# 2502_IDS_TransMax_PWM_Digital.net
KiCad netlist of a schematic drawn in Altium Designer
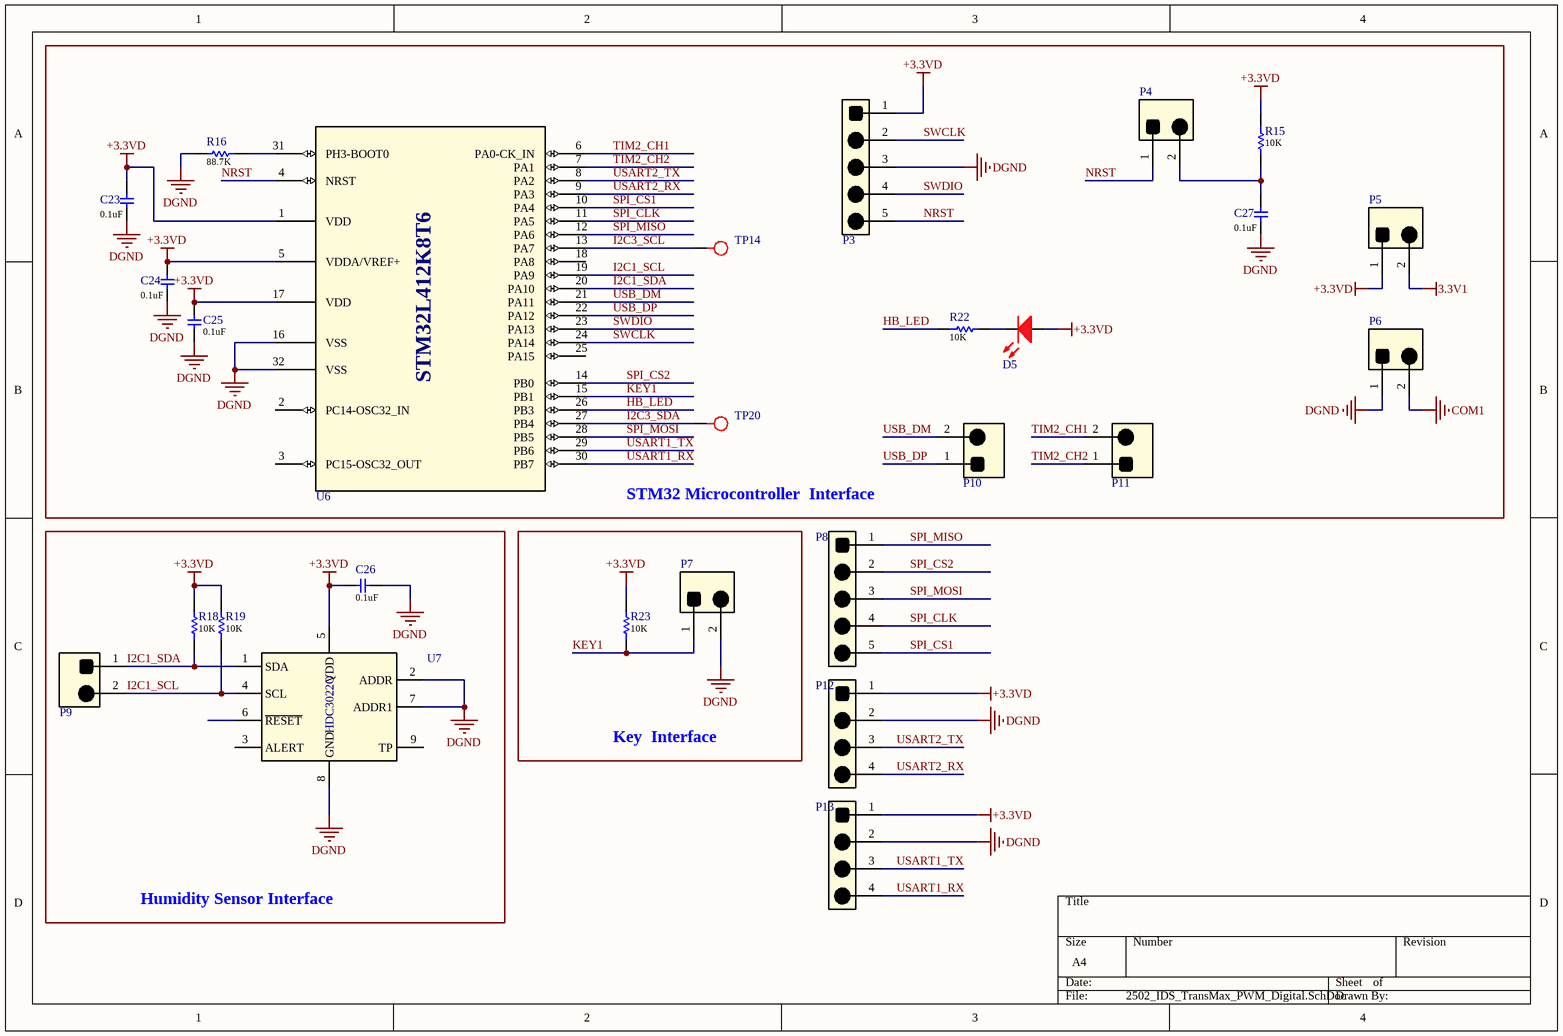
[diagram p0: 2502_IDS_TransMax_PWM_Digital.SchDoc]

(export (version "E")
  (design (tool "Eeschema 10.0.6"))
  (components
    (comp (ref "C23")
      (value "0.1uF")
      (footprint "C_0603 (1608 Metric)")
      (fields
        (field (name "MANUFACTURER PART NUMBER") "0603B104K101CT")
        (field (name "MANUFACTURER") "Walsin Technology Corporation")
        (field (name "Comment") "CAP CER 0.1UF 100V X7R 0603")
      )
      (libsource (lib "Capacitor") (part "CAP CER 0.1UF 100V X7R 0603"))
    )
    (comp (ref "C24")
      (value "0.1uF")
      (footprint "C_0603 (1608 Metric)")
      (fields
        (field (name "MANUFACTURER PART NUMBER") "0603B104K101CT")
        (field (name "MANUFACTURER") "Walsin Technology Corporation")
        (field (name "Comment") "CAP CER 0.1UF 100V X7R 0603")
      )
      (libsource (lib "Capacitor") (part "CAP CER 0.1UF 100V X7R 0603"))
    )
    (comp (ref "C25")
      (value "0.1uF")
      (footprint "C_0603 (1608 Metric)")
      (fields
        (field (name "MANUFACTURER PART NUMBER") "0603B104K101CT")
        (field (name "MANUFACTURER") "Walsin Technology Corporation")
        (field (name "Comment") "CAP CER 0.1UF 100V X7R 0603")
      )
      (libsource (lib "Capacitor") (part "CAP CER 0.1UF 100V X7R 0603"))
    )
    (comp (ref "C26")
      (value "0.1uF")
      (footprint "C_0603 (1608 Metric)")
      (fields
        (field (name "MANUFACTURER PART NUMBER") "0603B104K101CT")
        (field (name "MANUFACTURER") "Walsin Technology Corporation")
        (field (name "Comment") "CAP CER 0.1UF 100V X7R 0603")
      )
      (libsource (lib "Capacitor") (part "CAP CER 0.1UF 100V X7R 0603"))
    )
    (comp (ref "C27")
      (value "0.1uF")
      (footprint "C_0603 (1608 Metric)")
      (fields
        (field (name "MANUFACTURER PART NUMBER") "0603B104K101CT")
        (field (name "MANUFACTURER") "Walsin Technology Corporation")
        (field (name "Comment") "CAP CER 0.1UF 100V X7R 0603")
      )
      (libsource (lib "Capacitor") (part "CAP CER 0.1UF 100V X7R 0603"))
    )
    (comp (ref "D5")
      (value "LED RED CLEAR 0805 SMD")
      (footprint "L_SMD0805")
      (fields (field (name "MANUFACTURER PART NO") "EAST2012RA2"))
      (libsource (lib "Diode") (part "LED RED CLEAR 0805 SMD"))
    )
    (comp (ref "P3")
      (value "CONN HEADER VERT 5POS 2.54MM")
      (footprint "61300511121")
      (fields (field (name "MANUFACTURER PART NO") "61300511121"))
      (libsource (lib "Connector") (part "CONN HEADER VERT 5POS 2.54MM"))
    )
    (comp (ref "P4")
      (value "CONN HEADER VERT 2POS 2.54MM")
      (footprint "61300211121")
      (fields (field (name "MANUFACTURER PART NO") "61300211121"))
      (libsource (lib "") (part "CONN HEADER VERT 2POS 2.54MM_1"))
    )
    (comp (ref "P5")
      (value "CONN HEADER VERT 2POS 2.54MM")
      (footprint "61300211121")
      (fields (field (name "MANUFACTURER PART NO") "61300211121"))
      (libsource (lib "") (part "CONN HEADER VERT 2POS 2.54MM_1"))
    )
    (comp (ref "P6")
      (value "CONN HEADER VERT 2POS 2.54MM")
      (footprint "61300211121")
      (fields (field (name "MANUFACTURER PART NO") "61300211121"))
      (libsource (lib "") (part "CONN HEADER VERT 2POS 2.54MM_1"))
    )
    (comp (ref "P7")
      (value "CONN HEADER VERT 2POS 2.54MM")
      (footprint "61300211121")
      (fields (field (name "MANUFACTURER PART NO") "61300211121"))
      (libsource (lib "") (part "CONN HEADER VERT 2POS 2.54MM_1"))
    )
    (comp (ref "P8")
      (value "CONN HEADER VERT 5POS 2.54MM")
      (footprint "61300511121")
      (fields (field (name "MANUFACTURER PART NO") "61300511121"))
      (libsource (lib "Connector") (part "CONN HEADER VERT 5POS 2.54MM"))
    )
    (comp (ref "P9")
      (value "CONN HEADER VERT 2POS 2.54MM")
      (footprint "61300211121")
      (fields (field (name "MANUFACTURER PART NO") "61300211121"))
      (libsource (lib "Connector") (part "CONN HEADER VERT 2POS 2.54MM"))
    )
    (comp (ref "P10")
      (value "CONN HEADER VERT 2POS 2.54MM")
      (footprint "61300211121")
      (fields (field (name "MANUFACTURER PART NO") "61300211121"))
      (libsource (lib "") (part "CONN HEADER VERT 2POS 2.54MM_1"))
    )
    (comp (ref "P11")
      (value "CONN HEADER VERT 2POS 2.54MM")
      (footprint "61300211121")
      (fields (field (name "MANUFACTURER PART NO") "61300211121"))
      (libsource (lib "") (part "CONN HEADER VERT 2POS 2.54MM_1"))
    )
    (comp (ref "P12")
      (value "CONN HEADER VERT 4POS 2.54MM")
      (footprint "61300411121")
      (fields (field (name "MANUFACTURER PART NO") "61300411121"))
      (libsource (lib "Connector") (part "CONN HEADER VERT 4POS 2.54MM"))
    )
    (comp (ref "P13")
      (value "CONN HEADER VERT 4POS 2.54MM")
      (footprint "61300411121")
      (fields (field (name "MANUFACTURER PART NO") "61300411121"))
      (libsource (lib "Connector") (part "CONN HEADER VERT 4POS 2.54MM"))
    )
    (comp (ref "R15")
      (value "10K")
      (footprint "0603 (1608 Metric)")
      (fields
        (field (name "MANUFACTURER PART NO") "RMCF0603FT10K0")
        (field (name "Comment") "RES 10K OHM 1% 1/10W 0603")
      )
      (libsource (lib "Resistor") (part "RES 10K OHM 1% 1/10W 0603"))
    )
    (comp (ref "R16")
      (value "88.7K")
      (footprint "0805 (2012 Metric)")
      (fields
        (field (name "MANUFACTURER PART NO") "RC0805FR-0788K7L")
        (field (name "Comment") "RES 88.7K OHM 1% 1/8W 0805")
      )
      (libsource (lib "Resistor") (part "RES 88.7K OHM 1% 1/8W 0805"))
    )
    (comp (ref "R18")
      (value "10K")
      (footprint "0603 (1608 Metric)")
      (fields
        (field (name "MANUFACTURER PART NO") "RMCF0603FT10K0")
        (field (name "Comment") "RES 10K OHM 1% 1/10W 0603")
      )
      (libsource (lib "Resistor") (part "RES 10K OHM 1% 1/10W 0603"))
    )
    (comp (ref "R19")
      (value "10K")
      (footprint "0603 (1608 Metric)")
      (fields
        (field (name "MANUFACTURER PART NO") "RMCF0603FT10K0")
        (field (name "Comment") "RES 10K OHM 1% 1/10W 0603")
      )
      (libsource (lib "Resistor") (part "RES 10K OHM 1% 1/10W 0603"))
    )
    (comp (ref "R22")
      (value "10K")
      (footprint "0603 (1608 Metric)")
      (fields
        (field (name "MANUFACTURER PART NO") "RMCF0603FT10K0")
        (field (name "Comment") "RES 10K OHM 1% 1/10W 0603")
      )
      (libsource (lib "Resistor") (part "RES 10K OHM 1% 1/10W 0603"))
    )
    (comp (ref "R23")
      (value "10K")
      (footprint "0603 (1608 Metric)")
      (fields
        (field (name "MANUFACTURER PART NO") "RMCF0603FT10K0")
        (field (name "Comment") "RES 10K OHM 1% 1/10W 0603")
      )
      (libsource (lib "Resistor") (part "RES 10K OHM 1% 1/10W 0603"))
    )
    (comp (ref "TP14")
      (value "Test Point")
      (footprint "Testpoint PTH")
      (libsource (lib "Connector") (part "Test Point"))
    )
    (comp (ref "TP20")
      (value "Test Point")
      (footprint "Testpoint PTH")
      (libsource (lib "Connector") (part "Test Point"))
    )
    (comp (ref "U6")
      (value "IC STM32L412K8T6 32-LQFP")
      (footprint "32-LQFP")
      (fields (field (name "MANUFACTURER PART NO") "STM32L412K8T6"))
      (libsource (lib "IC") (part "STM32L412K8T6"))
    )
    (comp (ref "U7")
      (value "RH DIGITAL HUMIDITY SENSOR")
      (footprint "8-LFDFN Exposed Pad")
      (fields (field (name "MANUFACTURER PART NO") "HDC3022QDEJRQ1"))
      (libsource (lib "IC") (part "HDC3022QDEJRQ1"))
    )
  )
  (nets
    (net (code "1") (name "+3.3VD") (class "Default")
      (node (ref "C23") (pin "2") (pinfunction "2_2") (pintype "passive"))
      (node (ref "C24") (pin "2") (pinfunction "2_2") (pintype "passive"))
      (node (ref "C25") (pin "2") (pinfunction "2_2") (pintype "passive"))
      (node (ref "C26") (pin "2") (pinfunction "2_2") (pintype "passive"))
      (node (ref "D5") (pin "1") (pinfunction "A_1") (pintype "passive"))
      (node (ref "P12") (pin "1") (pinfunction "1_1") (pintype "passive"))
      (node (ref "P13") (pin "1") (pinfunction "1_1") (pintype "passive"))
      (node (ref "P3") (pin "1") (pinfunction "1_1") (pintype "passive"))
      (node (ref "P5") (pin "1") (pinfunction "1_1") (pintype "passive"))
      (node (ref "R15") (pin "2") (pinfunction "2_2") (pintype "passive"))
      (node (ref "R18") (pin "1") (pinfunction "1_1") (pintype "passive"))
      (node (ref "R19") (pin "1") (pinfunction "1_1") (pintype "passive"))
      (node (ref "R23") (pin "1") (pinfunction "1_1") (pintype "passive"))
      (node (ref "U6") (pin "1") (pinfunction "VDD_1") (pintype "power_in"))
      (node (ref "U6") (pin "17") (pinfunction "VDD_17") (pintype "power_in"))
      (node (ref "U6") (pin "5") (pinfunction "VDDA/VREF+_5") (pintype "power_in"))
      (node (ref "U7") (pin "5") (pinfunction "VDD_5") (pintype "open_collector"))
    )
    (net (code "2") (name "/HB_LED") (class "Default")
      (node (ref "R22") (pin "2") (pinfunction "2_2") (pintype "passive"))
      (node (ref "U6") (pin "26") (pinfunction "PB3_26") (pintype "bidirectional"))
    )
    (net (code "3") (name "/I2C1_SCL") (class "Default")
      (node (ref "P9") (pin "2") (pinfunction "2_2") (pintype "passive"))
      (node (ref "R19") (pin "2") (pinfunction "2_2") (pintype "passive"))
      (node (ref "U6") (pin "19") (pinfunction "PA9_19") (pintype "bidirectional"))
      (node (ref "U7") (pin "4") (pinfunction "SCL_4") (pintype "open_collector"))
    )
    (net (code "4") (name "/I2C1_SDA") (class "Default")
      (node (ref "P9") (pin "1") (pinfunction "1_1") (pintype "passive"))
      (node (ref "R18") (pin "2") (pinfunction "2_2") (pintype "passive"))
      (node (ref "U6") (pin "20") (pinfunction "PA10_20") (pintype "bidirectional"))
      (node (ref "U7") (pin "1") (pinfunction "SDA_1") (pintype "power_in"))
    )
    (net (code "5") (name "/I2C3_SCL") (class "Default")
      (node (ref "TP14") (pin "1") (pinfunction "1_1") (pintype "passive"))
      (node (ref "U6") (pin "13") (pinfunction "PA7_13") (pintype "bidirectional"))
    )
    (net (code "6") (name "/I2C3_SDA") (class "Default")
      (node (ref "TP20") (pin "1") (pinfunction "1_1") (pintype "passive"))
      (node (ref "U6") (pin "27") (pinfunction "PB4_27") (pintype "bidirectional"))
    )
    (net (code "7") (name "/KEY1") (class "Default")
      (node (ref "P7") (pin "1") (pinfunction "1_1") (pintype "passive"))
      (node (ref "R23") (pin "2") (pinfunction "2_2") (pintype "passive"))
      (node (ref "U6") (pin "15") (pinfunction "PB1_15") (pintype "bidirectional"))
    )
    (net (code "8") (name "/NRST") (class "Default")
      (node (ref "P3") (pin "5") (pinfunction "5_5") (pintype "passive"))
      (node (ref "P4") (pin "1") (pinfunction "1_1") (pintype "passive"))
      (node (ref "U6") (pin "4") (pinfunction "NRST_4") (pintype "bidirectional"))
    )
    (net (code "9") (name "/SPI_CLK") (class "Default")
      (node (ref "P8") (pin "4") (pinfunction "4_4") (pintype "passive"))
      (node (ref "U6") (pin "11") (pinfunction "PA5_11") (pintype "bidirectional"))
    )
    (net (code "10") (name "/SPI_CS1") (class "Default")
      (node (ref "P8") (pin "5") (pinfunction "5_5") (pintype "passive"))
      (node (ref "U6") (pin "10") (pinfunction "PA4_10") (pintype "bidirectional"))
    )
    (net (code "11") (name "/SPI_CS2") (class "Default")
      (node (ref "P8") (pin "2") (pinfunction "2_2") (pintype "passive"))
      (node (ref "U6") (pin "14") (pinfunction "PB0_14") (pintype "bidirectional"))
    )
    (net (code "12") (name "/SPI_MISO") (class "Default")
      (node (ref "P8") (pin "1") (pinfunction "1_1") (pintype "passive"))
      (node (ref "U6") (pin "12") (pinfunction "PA6_12") (pintype "bidirectional"))
    )
    (net (code "13") (name "/SPI_MOSI") (class "Default")
      (node (ref "P8") (pin "3") (pinfunction "3_3") (pintype "passive"))
      (node (ref "U6") (pin "28") (pinfunction "PB5_28") (pintype "bidirectional"))
    )
    (net (code "14") (name "/SWCLK") (class "Default")
      (node (ref "P3") (pin "2") (pinfunction "2_2") (pintype "passive"))
      (node (ref "U6") (pin "24") (pinfunction "PA14_24") (pintype "bidirectional"))
    )
    (net (code "15") (name "/SWDIO") (class "Default")
      (node (ref "P3") (pin "4") (pinfunction "4_4") (pintype "passive"))
      (node (ref "U6") (pin "23") (pinfunction "PA13_23") (pintype "bidirectional"))
    )
    (net (code "16") (name "/TIM2_CH1") (class "Default")
      (node (ref "P11") (pin "2") (pinfunction "2_2") (pintype "passive"))
      (node (ref "U6") (pin "6") (pinfunction "PA0-CK_IN_6") (pintype "bidirectional"))
    )
    (net (code "17") (name "/TIM2_CH2") (class "Default")
      (node (ref "P11") (pin "1") (pinfunction "1_1") (pintype "passive"))
      (node (ref "U6") (pin "7") (pinfunction "PA1_7") (pintype "bidirectional"))
    )
    (net (code "18") (name "/USART1_RX") (class "Default")
      (node (ref "P13") (pin "4") (pinfunction "4_4") (pintype "passive"))
      (node (ref "U6") (pin "30") (pinfunction "PB7_30") (pintype "bidirectional"))
    )
    (net (code "19") (name "/USART1_TX") (class "Default")
      (node (ref "P13") (pin "3") (pinfunction "3_3") (pintype "passive"))
      (node (ref "U6") (pin "29") (pinfunction "PB6_29") (pintype "bidirectional"))
    )
    (net (code "20") (name "/USART2_RX") (class "Default")
      (node (ref "P12") (pin "4") (pinfunction "4_4") (pintype "passive"))
      (node (ref "U6") (pin "9") (pinfunction "PA3_9") (pintype "bidirectional"))
    )
    (net (code "21") (name "/USART2_TX") (class "Default")
      (node (ref "P12") (pin "3") (pinfunction "3_3") (pintype "passive"))
      (node (ref "U6") (pin "8") (pinfunction "PA2_8") (pintype "bidirectional"))
    )
    (net (code "22") (name "/USB_DM") (class "Default")
      (node (ref "P10") (pin "2") (pinfunction "2_2") (pintype "passive"))
      (node (ref "U6") (pin "21") (pinfunction "PA11_21") (pintype "bidirectional"))
    )
    (net (code "23") (name "/USB_DP") (class "Default")
      (node (ref "P10") (pin "1") (pinfunction "1_1") (pintype "passive"))
      (node (ref "U6") (pin "22") (pinfunction "PA12_22") (pintype "bidirectional"))
    )
    (net (code "24") (name "3.3V1") (class "Default")
      (node (ref "P5") (pin "2") (pinfunction "2_2") (pintype "passive"))
    )
    (net (code "25") (name "COM1") (class "Default")
      (node (ref "P6") (pin "2") (pinfunction "2_2") (pintype "passive"))
    )
    (net (code "26") (name "DGND") (class "Default")
      (node (ref "C23") (pin "1") (pinfunction "1_1") (pintype "passive"))
      (node (ref "C24") (pin "1") (pinfunction "1_1") (pintype "passive"))
      (node (ref "C25") (pin "1") (pinfunction "1_1") (pintype "passive"))
      (node (ref "C26") (pin "1") (pinfunction "1_1") (pintype "passive"))
      (node (ref "C27") (pin "1") (pinfunction "1_1") (pintype "passive"))
      (node (ref "P12") (pin "2") (pinfunction "2_2") (pintype "passive"))
      (node (ref "P13") (pin "2") (pinfunction "2_2") (pintype "passive"))
      (node (ref "P3") (pin "3") (pinfunction "3_3") (pintype "passive"))
      (node (ref "P6") (pin "1") (pinfunction "1_1") (pintype "passive"))
      (node (ref "P7") (pin "2") (pinfunction "2_2") (pintype "passive"))
      (node (ref "R16") (pin "1") (pinfunction "1_1") (pintype "passive"))
      (node (ref "U6") (pin "16") (pinfunction "VSS_16") (pintype "power_in"))
      (node (ref "U6") (pin "32") (pinfunction "VSS_32") (pintype "power_in"))
      (node (ref "U7") (pin "2") (pinfunction "ADDR_2") (pintype "power_in"))
      (node (ref "U7") (pin "7") (pinfunction "ADDR1_7") (pintype "open_collector"))
      (node (ref "U7") (pin "8") (pinfunction "GND_8") (pintype "power_in"))
    )
    (net (code "27") (name "Net-(C27-Pad2)") (class "Default")
      (node (ref "C27") (pin "2") (pinfunction "2_2") (pintype "passive"))
      (node (ref "P4") (pin "2") (pinfunction "2_2") (pintype "passive"))
      (node (ref "R15") (pin "1") (pinfunction "1_1") (pintype "passive"))
    )
    (net (code "28") (name "Net-(D5-K)") (class "Default")
      (node (ref "D5") (pin "2") (pinfunction "K_2") (pintype "passive"))
      (node (ref "R22") (pin "1") (pinfunction "1_1") (pintype "passive"))
    )
    (net (code "29") (name "Net-(U6-PH3-BOOT0)") (class "Default")
      (node (ref "R16") (pin "2") (pinfunction "2_2") (pintype "passive"))
      (node (ref "U6") (pin "31") (pinfunction "PH3-BOOT0_31") (pintype "bidirectional"))
    )
    (net (code "30") (name "unconnected-(U6-PA8-Pad18)") (class "Default")
      (node (ref "U6") (pin "18") (pinfunction "PA8_18") (pintype "bidirectional"))
    )
    (net (code "31") (name "unconnected-(U6-PA15-Pad25)") (class "Default")
      (node (ref "U6") (pin "25") (pinfunction "PA15_25") (pintype "bidirectional"))
    )
    (net (code "32") (name "unconnected-(U6-PC14-OSC32_IN-Pad2)") (class "Default")
      (node (ref "U6") (pin "2") (pinfunction "PC14-OSC32_IN_2") (pintype "bidirectional"))
    )
    (net (code "33") (name "unconnected-(U6-PC15-OSC32_OUT-Pad3)") (class "Default")
      (node (ref "U6") (pin "3") (pinfunction "PC15-OSC32_OUT_3") (pintype "bidirectional"))
    )
    (net (code "34") (name "unconnected-(U7-ALERT-Pad3)") (class "Default")
      (node (ref "U7") (pin "3") (pinfunction "ALERT_3") (pintype "open_collector"))
    )
    (net (code "35") (name "unconnected-(U7-TP-Pad9)") (class "Default")
      (node (ref "U7") (pin "9") (pinfunction "TP_9") (pintype "power_in"))
    )
    (net (code "36") (name "unconnected-(U7-~{RESET}-Pad6)") (class "Default")
      (node (ref "U7") (pin "6") (pinfunction "~{RESET}_6") (pintype "open_collector"))
    )
  )
)
